# DASH_MICROCONTROLLER.net
KiCad netlist of a schematic drawn in Altium Designer
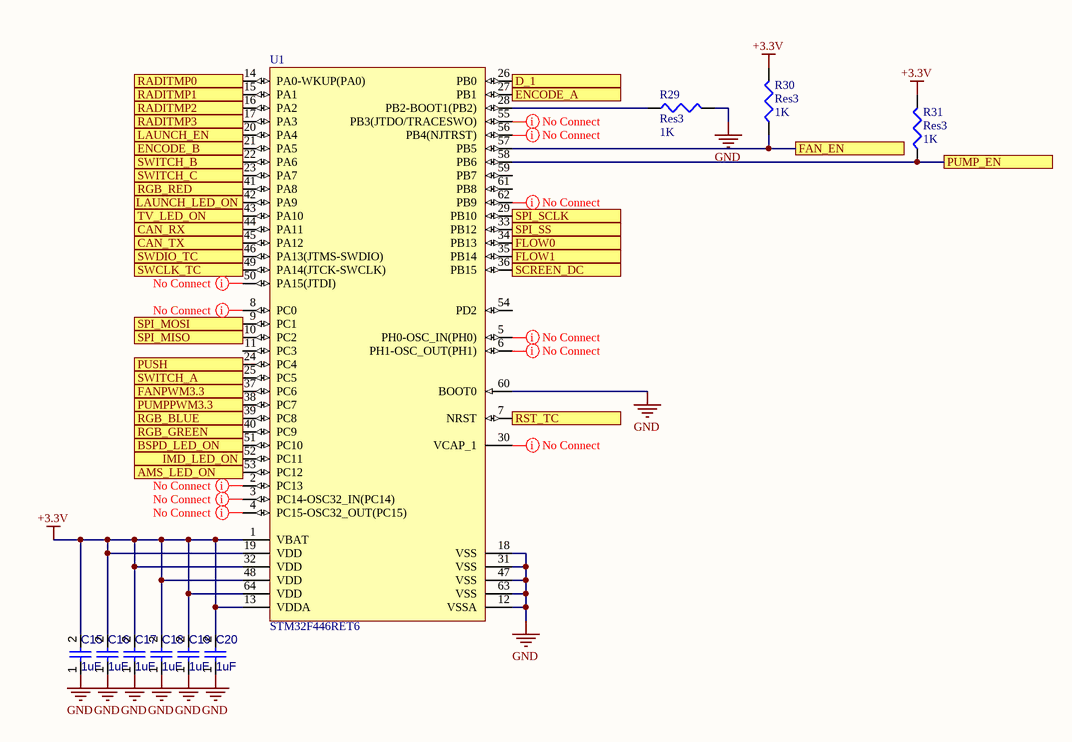
[diagram p0: DASH_MICROCONTROLLER.SchDoc]

(export (version "E")
  (design (tool "Eeschema 10.0.6"))
  (components
    (comp (ref "C15")
      (value "1uF")
      (footprint "CAPC0603(1608)100_L")
      (description "Chip Capacitor, 1 uF, +/- 10%, 6.3 V, 0402 (1005 Metric)")
      (fields (field (name "AVAILABLE PREVIEW IMAGES") "2D"))
      (libsource (lib "Illini Formula Electric") (part "Symbol"))
    )
    (comp (ref "C16")
      (value "1uF")
      (footprint "CAPC0603(1608)100_L")
      (description "Chip Capacitor, 1 uF, +/- 10%, 6.3 V, 0402 (1005 Metric)")
      (fields (field (name "AVAILABLE PREVIEW IMAGES") "2D"))
      (libsource (lib "Illini Formula Electric") (part "Symbol"))
    )
    (comp (ref "C17")
      (value "1uF")
      (footprint "CAPC0603(1608)100_L")
      (description "Chip Capacitor, 1 uF, +/- 10%, 6.3 V, 0402 (1005 Metric)")
      (fields (field (name "AVAILABLE PREVIEW IMAGES") "2D"))
      (libsource (lib "Illini Formula Electric") (part "Symbol"))
    )
    (comp (ref "C18")
      (value "1uF")
      (footprint "CAPC0603(1608)100_L")
      (description "Chip Capacitor, 1 uF, +/- 10%, 6.3 V, 0402 (1005 Metric)")
      (fields (field (name "AVAILABLE PREVIEW IMAGES") "2D"))
      (libsource (lib "Illini Formula Electric") (part "Symbol"))
    )
    (comp (ref "C19")
      (value "1uF")
      (footprint "CAPC0603(1608)100_L")
      (description "Chip Capacitor, 1 uF, +/- 10%, 6.3 V, 0402 (1005 Metric)")
      (fields (field (name "AVAILABLE PREVIEW IMAGES") "2D"))
      (libsource (lib "Illini Formula Electric") (part "Symbol"))
    )
    (comp (ref "C20")
      (value "1uF")
      (footprint "CAPC0603(1608)100_L")
      (description "Chip Capacitor, 1 uF, +/- 10%, 6.3 V, 0402 (1005 Metric)")
      (fields (field (name "AVAILABLE PREVIEW IMAGES") "2D"))
      (libsource (lib "Illini Formula Electric") (part "Symbol"))
    )
    (comp (ref "R29")
      (value "Res3")
      (footprint "J1-0603")
      (description "Resistor")
      (fields (field (name "ALTIUM_VALUE") "1K") (field (name "PUBLISHER") "Altium Limited"))
      (libsource (lib "Miscellaneous Devices") (part "Res3"))
    )
    (comp (ref "R30")
      (value "Res3")
      (footprint "J1-0603")
      (description "Resistor")
      (fields (field (name "ALTIUM_VALUE") "1K") (field (name "PUBLISHER") "Altium Limited"))
      (libsource (lib "Miscellaneous Devices") (part "Res3"))
    )
    (comp (ref "R31")
      (value "Res3")
      (footprint "J1-0603")
      (description "Resistor")
      (fields (field (name "ALTIUM_VALUE") "1K") (field (name "PUBLISHER") "Altium Limited"))
      (libsource (lib "Miscellaneous Devices") (part "Res3"))
    )
    (comp (ref "U1")
      (value "STM32F446RET6")
      (footprint "STM-LQFP64_L")
      (libsource (lib "Altium Content Vault") (part "MC-ARM-STM32F446-LQFP64"))
    )
  )
  (nets
    (net (code "1") (name "+3.3V") (class "Default")
      (node (ref "C15") (pin "2") (pinfunction "2_2") (pintype "passive"))
      (node (ref "C16") (pin "2") (pinfunction "2_2") (pintype "passive"))
      (node (ref "C17") (pin "2") (pinfunction "2_2") (pintype "passive"))
      (node (ref "C18") (pin "2") (pinfunction "2_2") (pintype "passive"))
      (node (ref "C19") (pin "2") (pinfunction "2_2") (pintype "passive"))
      (node (ref "C20") (pin "2") (pinfunction "2_2") (pintype "passive"))
      (node (ref "R30") (pin "2") (pinfunction "2_2") (pintype "passive"))
      (node (ref "R31") (pin "2") (pinfunction "2_2") (pintype "passive"))
      (node (ref "U1") (pin "1") (pinfunction "VBAT_1") (pintype "power_in"))
      (node (ref "U1") (pin "13") (pinfunction "VDDA_13") (pintype "power_in"))
      (node (ref "U1") (pin "19") (pinfunction "VDD_19") (pintype "power_in"))
      (node (ref "U1") (pin "32") (pinfunction "VDD_32") (pintype "power_in"))
      (node (ref "U1") (pin "48") (pinfunction "VDD_48") (pintype "power_in"))
      (node (ref "U1") (pin "64") (pinfunction "VDD_64") (pintype "power_in"))
    )
    (net (code "2") (name "/AMS_LED_ON") (class "Default")
      (node (ref "U1") (pin "53") (pinfunction "PC12_53") (pintype "bidirectional"))
    )
    (net (code "3") (name "/BSPD_LED_ON") (class "Default")
      (node (ref "U1") (pin "51") (pinfunction "PC10_51") (pintype "bidirectional"))
    )
    (net (code "4") (name "/CAN_RX") (class "Default")
      (node (ref "U1") (pin "44") (pinfunction "PA11_44") (pintype "bidirectional"))
    )
    (net (code "5") (name "/CAN_TX") (class "Default")
      (node (ref "U1") (pin "45") (pinfunction "PA12_45") (pintype "bidirectional"))
    )
    (net (code "6") (name "/D_1") (class "Default")
      (node (ref "U1") (pin "26") (pinfunction "PB0_26") (pintype "bidirectional"))
    )
    (net (code "7") (name "/ENCODE_A") (class "Default")
      (node (ref "U1") (pin "27") (pinfunction "PB1_27") (pintype "bidirectional"))
    )
    (net (code "8") (name "/ENCODE_B") (class "Default")
      (node (ref "U1") (pin "21") (pinfunction "PA5_21") (pintype "bidirectional"))
    )
    (net (code "9") (name "/FANPWM3.3") (class "Default")
      (node (ref "U1") (pin "37") (pinfunction "PC6_37") (pintype "bidirectional"))
    )
    (net (code "10") (name "/FAN_EN") (class "Default")
      (node (ref "R30") (pin "1") (pinfunction "1_1") (pintype "passive"))
      (node (ref "U1") (pin "57") (pinfunction "PB5_57") (pintype "bidirectional"))
    )
    (net (code "11") (name "/FLOW0") (class "Default")
      (node (ref "U1") (pin "34") (pinfunction "PB13_34") (pintype "bidirectional"))
    )
    (net (code "12") (name "/FLOW1") (class "Default")
      (node (ref "U1") (pin "35") (pinfunction "PB14_35") (pintype "bidirectional"))
    )
    (net (code "13") (name "/IMD_LED_ON") (class "Default")
      (node (ref "U1") (pin "52") (pinfunction "PC11_52") (pintype "bidirectional"))
    )
    (net (code "14") (name "/LAUNCH_EN") (class "Default")
      (node (ref "U1") (pin "20") (pinfunction "PA4_20") (pintype "bidirectional"))
    )
    (net (code "15") (name "/LAUNCH_LED_ON") (class "Default")
      (node (ref "U1") (pin "42") (pinfunction "PA9_42") (pintype "bidirectional"))
    )
    (net (code "16") (name "/PUMPPWM3.3") (class "Default")
      (node (ref "U1") (pin "38") (pinfunction "PC7_38") (pintype "bidirectional"))
    )
    (net (code "17") (name "/PUMP_EN") (class "Default")
      (node (ref "R31") (pin "1") (pinfunction "1_1") (pintype "passive"))
      (node (ref "U1") (pin "58") (pinfunction "PB6_58") (pintype "bidirectional"))
    )
    (net (code "18") (name "/PUSH") (class "Default")
      (node (ref "U1") (pin "24") (pinfunction "PC4_24") (pintype "bidirectional"))
    )
    (net (code "19") (name "/RADITMP0") (class "Default")
      (node (ref "U1") (pin "14") (pinfunction "PA0-WKUP(PA0)_14") (pintype "bidirectional"))
    )
    (net (code "20") (name "/RADITMP1") (class "Default")
      (node (ref "U1") (pin "15") (pinfunction "PA1_15") (pintype "bidirectional"))
    )
    (net (code "21") (name "/RADITMP2") (class "Default")
      (node (ref "U1") (pin "16") (pinfunction "PA2_16") (pintype "bidirectional"))
    )
    (net (code "22") (name "/RADITMP3") (class "Default")
      (node (ref "U1") (pin "17") (pinfunction "PA3_17") (pintype "bidirectional"))
    )
    (net (code "23") (name "/RGB_BLUE") (class "Default")
      (node (ref "U1") (pin "39") (pinfunction "PC8_39") (pintype "bidirectional"))
    )
    (net (code "24") (name "/RGB_GREEN") (class "Default")
      (node (ref "U1") (pin "40") (pinfunction "PC9_40") (pintype "bidirectional"))
    )
    (net (code "25") (name "/RGB_RED") (class "Default")
      (node (ref "U1") (pin "41") (pinfunction "PA8_41") (pintype "bidirectional"))
    )
    (net (code "26") (name "/RST_TC") (class "Default")
      (node (ref "U1") (pin "7") (pinfunction "NRST_7") (pintype "bidirectional"))
    )
    (net (code "27") (name "/SCREEN_DC") (class "Default")
      (node (ref "U1") (pin "36") (pinfunction "PB15_36") (pintype "bidirectional"))
    )
    (net (code "28") (name "/SPI_MISO") (class "Default")
      (node (ref "U1") (pin "10") (pinfunction "PC2_10") (pintype "bidirectional"))
    )
    (net (code "29") (name "/SPI_MOSI") (class "Default")
      (node (ref "U1") (pin "9") (pinfunction "PC1_9") (pintype "bidirectional"))
    )
    (net (code "30") (name "/SPI_SCLK") (class "Default")
      (node (ref "U1") (pin "29") (pinfunction "PB10_29") (pintype "bidirectional"))
    )
    (net (code "31") (name "/SPI_SS") (class "Default")
      (node (ref "U1") (pin "33") (pinfunction "PB12_33") (pintype "bidirectional"))
    )
    (net (code "32") (name "/SWCLK_TC") (class "Default")
      (node (ref "U1") (pin "49") (pinfunction "PA14(JTCK-SWCLK)_49") (pintype "bidirectional"))
    )
    (net (code "33") (name "/SWDIO_TC") (class "Default")
      (node (ref "U1") (pin "46") (pinfunction "PA13(JTMS-SWDIO)_46") (pintype "bidirectional"))
    )
    (net (code "34") (name "/SWITCH_A") (class "Default")
      (node (ref "U1") (pin "25") (pinfunction "PC5_25") (pintype "bidirectional"))
    )
    (net (code "35") (name "/SWITCH_B") (class "Default")
      (node (ref "U1") (pin "22") (pinfunction "PA6_22") (pintype "bidirectional"))
    )
    (net (code "36") (name "/SWITCH_C") (class "Default")
      (node (ref "U1") (pin "23") (pinfunction "PA7_23") (pintype "bidirectional"))
    )
    (net (code "37") (name "/TV_LED_ON") (class "Default")
      (node (ref "U1") (pin "43") (pinfunction "PA10_43") (pintype "bidirectional"))
    )
    (net (code "38") (name "GND") (class "Default")
      (node (ref "C15") (pin "1") (pinfunction "1_1") (pintype "passive"))
      (node (ref "C16") (pin "1") (pinfunction "1_1") (pintype "passive"))
      (node (ref "C17") (pin "1") (pinfunction "1_1") (pintype "passive"))
      (node (ref "C18") (pin "1") (pinfunction "1_1") (pintype "passive"))
      (node (ref "C19") (pin "1") (pinfunction "1_1") (pintype "passive"))
      (node (ref "C20") (pin "1") (pinfunction "1_1") (pintype "passive"))
      (node (ref "R29") (pin "2") (pinfunction "2_2") (pintype "passive"))
      (node (ref "U1") (pin "12") (pinfunction "VSSA_12") (pintype "power_in"))
      (node (ref "U1") (pin "18") (pinfunction "VSS_18") (pintype "power_in"))
      (node (ref "U1") (pin "31") (pinfunction "VSS_31") (pintype "power_in"))
      (node (ref "U1") (pin "47") (pinfunction "VSS_47") (pintype "power_in"))
      (node (ref "U1") (pin "60") (pinfunction "BOOT0_60") (pintype "input"))
      (node (ref "U1") (pin "63") (pinfunction "VSS_63") (pintype "power_in"))
    )
    (net (code "39") (name "Net-(U1-PB2-BOOT1(PB2))") (class "Default")
      (node (ref "R29") (pin "1") (pinfunction "1_1") (pintype "passive"))
      (node (ref "U1") (pin "28") (pinfunction "PB2-BOOT1(PB2)_28") (pintype "bidirectional"))
    )
    (net (code "40") (name "unconnected-(U1-PA15(JTDI)-Pad50)") (class "Default")
      (node (ref "U1") (pin "50") (pinfunction "PA15(JTDI)_50") (pintype "bidirectional"))
    )
    (net (code "41") (name "unconnected-(U1-PB3(JTDO{slash}TRACESWO)-Pad55)") (class "Default")
      (node (ref "U1") (pin "55") (pinfunction "PB3(JTDO/TRACESWO)_55") (pintype "bidirectional"))
    )
    (net (code "42") (name "unconnected-(U1-PB4(NJTRST)-Pad56)") (class "Default")
      (node (ref "U1") (pin "56") (pinfunction "PB4(NJTRST)_56") (pintype "bidirectional"))
    )
    (net (code "43") (name "unconnected-(U1-PB7-Pad59)") (class "Default")
      (node (ref "U1") (pin "59") (pinfunction "PB7_59") (pintype "bidirectional"))
    )
    (net (code "44") (name "unconnected-(U1-PB8-Pad61)") (class "Default")
      (node (ref "U1") (pin "61") (pinfunction "PB8_61") (pintype "bidirectional"))
    )
    (net (code "45") (name "unconnected-(U1-PB9-Pad62)") (class "Default")
      (node (ref "U1") (pin "62") (pinfunction "PB9_62") (pintype "bidirectional"))
    )
    (net (code "46") (name "unconnected-(U1-PC0-Pad8)") (class "Default")
      (node (ref "U1") (pin "8") (pinfunction "PC0_8") (pintype "bidirectional"))
    )
    (net (code "47") (name "unconnected-(U1-PC3-Pad11)") (class "Default")
      (node (ref "U1") (pin "11") (pinfunction "PC3_11") (pintype "bidirectional"))
    )
    (net (code "48") (name "unconnected-(U1-PC13-Pad2)") (class "Default")
      (node (ref "U1") (pin "2") (pinfunction "PC13_2") (pintype "bidirectional"))
    )
    (net (code "49") (name "unconnected-(U1-PC14-OSC32_IN(PC14)-Pad3)") (class "Default")
      (node (ref "U1") (pin "3") (pinfunction "PC14-OSC32_IN(PC14)_3") (pintype "bidirectional"))
    )
    (net (code "50") (name "unconnected-(U1-PC15-OSC32_OUT(PC15)-Pad4)") (class "Default")
      (node (ref "U1") (pin "4") (pinfunction "PC15-OSC32_OUT(PC15)_4") (pintype "bidirectional"))
    )
    (net (code "51") (name "unconnected-(U1-PD2-Pad54)") (class "Default")
      (node (ref "U1") (pin "54") (pinfunction "PD2_54") (pintype "bidirectional"))
    )
    (net (code "52") (name "unconnected-(U1-PH0-OSC_IN(PH0)-Pad5)") (class "Default")
      (node (ref "U1") (pin "5") (pinfunction "PH0-OSC_IN(PH0)_5") (pintype "bidirectional"))
    )
    (net (code "53") (name "unconnected-(U1-PH1-OSC_OUT(PH1)-Pad6)") (class "Default")
      (node (ref "U1") (pin "6") (pinfunction "PH1-OSC_OUT(PH1)_6") (pintype "bidirectional"))
    )
    (net (code "54") (name "unconnected-(U1-VCAP_1-Pad30)") (class "Default")
      (node (ref "U1") (pin "30") (pinfunction "VCAP_1_30") (pintype "passive"))
    )
  )
)
